# WifeOLED.net
KiCad netlist of a schematic drawn in EAGLE
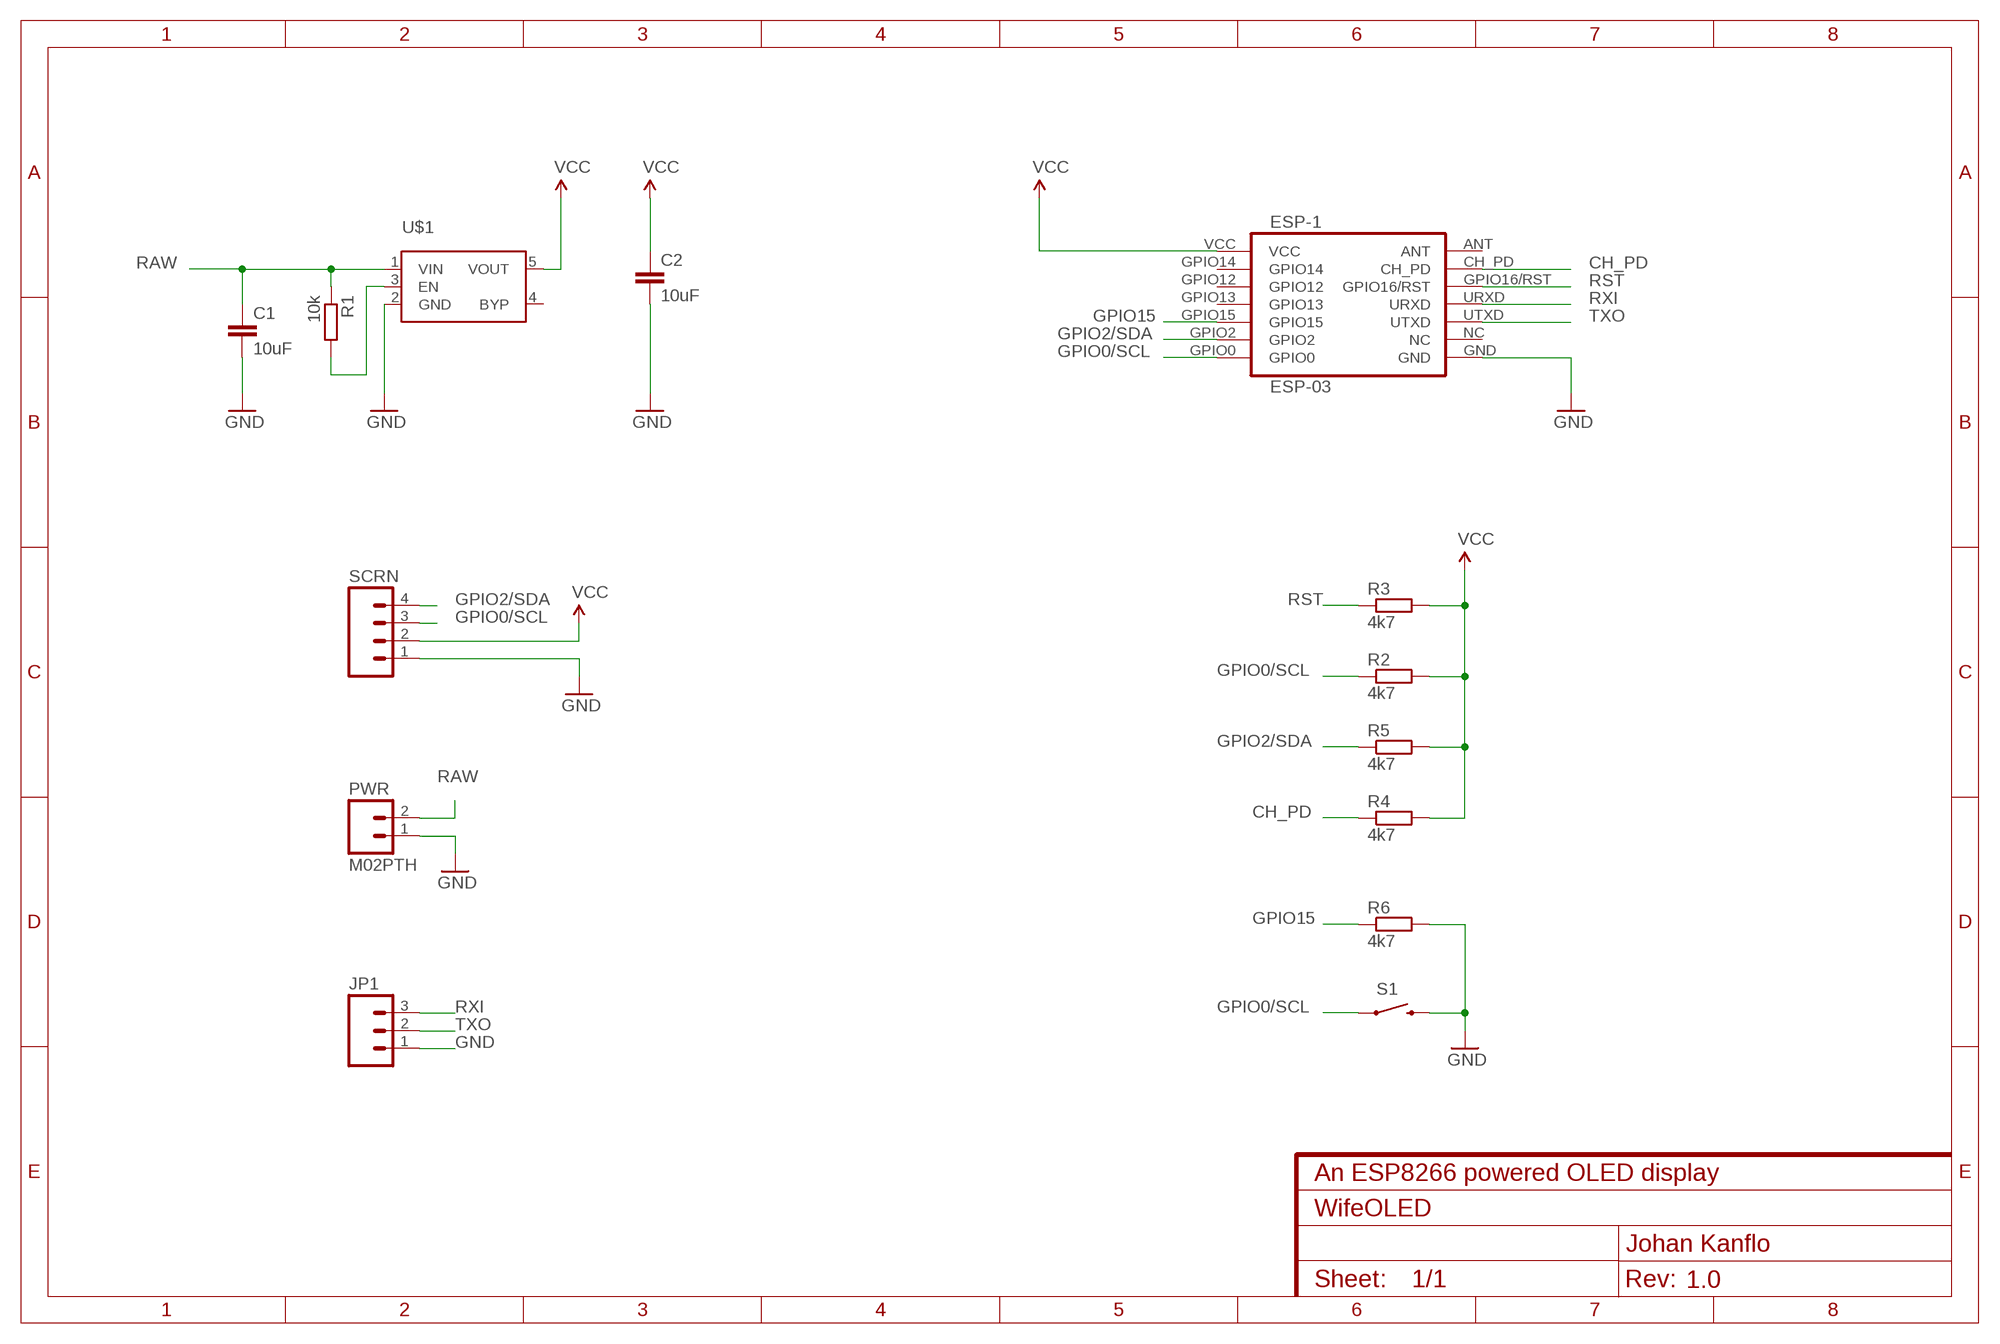
[diagram p0: schematic, sheet 1]

(export (version "E")
  (design (tool "Eeschema 10.0.6"))
  (components
    (comp (ref "C1")
      (value "10uF")
      (footprint "eagle-import:0603-CAP")
      (libsource (lib "eagle-import") (part "10UF-6.3V-20%(0603)"))
    )
    (comp (ref "C2")
      (value "10uF")
      (footprint "eagle-import:0603-CAP")
      (libsource (lib "eagle-import") (part "10UF-6.3V-20%(0603)"))
    )
    (comp (ref "ESP-1")
      (value "ESP-03")
      (footprint "eagle-import:ESP-03")
      (libsource (lib "eagle-import") (part "ESP-03"))
    )
    (comp (ref "JP1")
      (value "M03PTH")
      (footprint "eagle-import:1X03")
      (libsource (lib "eagle-import") (part "M03PTH"))
    )
    (comp (ref "PWR")
      (value "M02PTH")
      (footprint "eagle-import:1X02")
      (libsource (lib "eagle-import") (part "M02PTH"))
    )
    (comp (ref "R1")
      (value "10k")
      (footprint "eagle-import:R0603")
      (libsource (lib "eagle-import") (part "R-EU_R0603"))
    )
    (comp (ref "R2")
      (value "4k7")
      (footprint "eagle-import:R0603")
      (libsource (lib "eagle-import") (part "R-EU_R0603"))
    )
    (comp (ref "R3")
      (value "4k7")
      (footprint "eagle-import:R0603")
      (libsource (lib "eagle-import") (part "R-EU_R0603"))
    )
    (comp (ref "R4")
      (value "4k7")
      (footprint "eagle-import:R0603")
      (libsource (lib "eagle-import") (part "R-EU_R0603"))
    )
    (comp (ref "R5")
      (value "4k7")
      (footprint "eagle-import:R0603")
      (libsource (lib "eagle-import") (part "R-EU_R0603"))
    )
    (comp (ref "R6")
      (value "4k7")
      (footprint "eagle-import:R0603")
      (libsource (lib "eagle-import") (part "R-EU_R0603"))
    )
    (comp (ref "S1")
      (value "SWITCH-MOMENTARY-2SMD-1101NE")
      (footprint "eagle-import:TACTILE-SWITCH-1101NE")
      (libsource (lib "eagle-import") (part "SWITCH-MOMENTARY-2SMD-1101NE"))
    )
    (comp (ref "SCRN")
      (value "M04PTH")
      (footprint "eagle-import:1X04")
      (libsource (lib "eagle-import") (part "M04PTH"))
    )
    (comp (ref "U$1")
      (value "SPX3819")
      (footprint "eagle-import:SOT23-5")
      (libsource (lib "eagle-import") (part "SPX3819"))
    )
  )
  (nets
    (net (code "1") (name "/CH_PD") (class "Default")
      (node (ref "ESP-1") (pin "CH_PD") (pinfunction "CH_PD_CH_PD") (pintype "bidirectional"))
      (node (ref "R4") (pin "1") (pinfunction "1_1") (pintype "passive"))
    )
    (net (code "2") (name "/GPIO0{slash}SCL") (class "Default")
      (node (ref "ESP-1") (pin "GPIO0") (pinfunction "GPIO0_GPIO0") (pintype "bidirectional"))
      (node (ref "R2") (pin "1") (pinfunction "1_1") (pintype "passive"))
      (node (ref "S1") (pin "1") (pinfunction "1_1") (pintype "passive"))
      (node (ref "SCRN") (pin "3") (pinfunction "3_3") (pintype "passive"))
    )
    (net (code "3") (name "/GPIO2{slash}SDA") (class "Default")
      (node (ref "ESP-1") (pin "GPIO2") (pinfunction "GPIO2_GPIO2") (pintype "bidirectional"))
      (node (ref "R5") (pin "1") (pinfunction "1_1") (pintype "passive"))
      (node (ref "SCRN") (pin "4") (pinfunction "4_4") (pintype "passive"))
    )
    (net (code "4") (name "/GPIO15") (class "Default")
      (node (ref "ESP-1") (pin "GPIO15") (pinfunction "GPIO15_GPIO15") (pintype "bidirectional"))
      (node (ref "R6") (pin "1") (pinfunction "1_1") (pintype "passive"))
    )
    (net (code "5") (name "/RAW") (class "Default")
      (node (ref "C1") (pin "1") (pinfunction "1_1") (pintype "passive"))
      (node (ref "PWR") (pin "2") (pinfunction "2_2") (pintype "passive"))
      (node (ref "R1") (pin "1") (pinfunction "1_1") (pintype "passive"))
      (node (ref "U$1") (pin "1") (pinfunction "VIN_1") (pintype "power_in"))
    )
    (net (code "6") (name "/RST") (class "Default")
      (node (ref "ESP-1") (pin "GPIO16/RST") (pinfunction "GPIO16/RST_GPIO16/RST") (pintype "bidirectional"))
      (node (ref "R3") (pin "1") (pinfunction "1_1") (pintype "passive"))
    )
    (net (code "7") (name "/RXI") (class "Default")
      (node (ref "ESP-1") (pin "URXD") (pinfunction "URXD_URXD") (pintype "bidirectional"))
      (node (ref "JP1") (pin "3") (pinfunction "3_3") (pintype "passive"))
    )
    (net (code "8") (name "/TXO") (class "Default")
      (node (ref "ESP-1") (pin "UTXD") (pinfunction "UTXD_UTXD") (pintype "bidirectional"))
      (node (ref "JP1") (pin "2") (pinfunction "2_2") (pintype "passive"))
    )
    (net (code "9") (name "GND") (class "Default")
      (node (ref "C1") (pin "2") (pinfunction "2_2") (pintype "passive"))
      (node (ref "C2") (pin "2") (pinfunction "2_2") (pintype "passive"))
      (node (ref "ESP-1") (pin "GND") (pinfunction "GND_GND") (pintype "power_in"))
      (node (ref "JP1") (pin "1") (pinfunction "1_1") (pintype "passive"))
      (node (ref "PWR") (pin "1") (pinfunction "1_1") (pintype "passive"))
      (node (ref "R6") (pin "2") (pinfunction "2_2") (pintype "passive"))
      (node (ref "S1") (pin "2") (pinfunction "2_2") (pintype "passive"))
      (node (ref "SCRN") (pin "1") (pinfunction "1_1") (pintype "passive"))
      (node (ref "U$1") (pin "2") (pinfunction "GND_2") (pintype "power_in"))
    )
    (net (code "10") (name "Net-(U$1-EN)") (class "Default")
      (node (ref "R1") (pin "2") (pinfunction "2_2") (pintype "passive"))
      (node (ref "U$1") (pin "3") (pinfunction "EN_3") (pintype "input"))
    )
    (net (code "11") (name "VCC") (class "Default")
      (node (ref "C2") (pin "1") (pinfunction "1_1") (pintype "passive"))
      (node (ref "ESP-1") (pin "VCC") (pinfunction "VCC_VCC") (pintype "power_in"))
      (node (ref "R2") (pin "2") (pinfunction "2_2") (pintype "passive"))
      (node (ref "R3") (pin "2") (pinfunction "2_2") (pintype "passive"))
      (node (ref "R4") (pin "2") (pinfunction "2_2") (pintype "passive"))
      (node (ref "R5") (pin "2") (pinfunction "2_2") (pintype "passive"))
      (node (ref "SCRN") (pin "2") (pinfunction "2_2") (pintype "passive"))
      (node (ref "U$1") (pin "5") (pinfunction "VOUT_5") (pintype "output"))
    )
    (net (code "12") (name "unconnected-(ESP-1-PadANT)") (class "Default")
      (node (ref "ESP-1") (pin "ANT") (pinfunction "ANT_ANT") (pintype "bidirectional"))
    )
    (net (code "13") (name "unconnected-(ESP-1-PadGPIO12)") (class "Default")
      (node (ref "ESP-1") (pin "GPIO12") (pinfunction "GPIO12_GPIO12") (pintype "bidirectional"))
    )
    (net (code "14") (name "unconnected-(ESP-1-PadGPIO13)") (class "Default")
      (node (ref "ESP-1") (pin "GPIO13") (pinfunction "GPIO13_GPIO13") (pintype "bidirectional"))
    )
    (net (code "15") (name "unconnected-(ESP-1-PadGPIO14)") (class "Default")
      (node (ref "ESP-1") (pin "GPIO14") (pinfunction "GPIO14_GPIO14") (pintype "bidirectional"))
    )
    (net (code "16") (name "unconnected-(ESP-1-PadNC)") (class "Default")
      (node (ref "ESP-1") (pin "NC") (pinfunction "NC_NC") (pintype "bidirectional"))
    )
    (net (code "17") (name "unconnected-(U$1-BYP-Pad4)") (class "Default")
      (node (ref "U$1") (pin "4") (pinfunction "BYP_4") (pintype "output"))
    )
  )
)
